# output_led.net
KiCad netlist of a schematic drawn in EAGLE
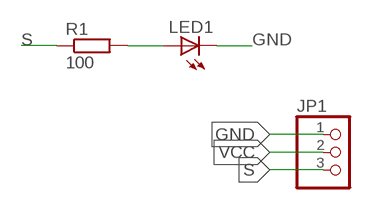
[diagram p0: schematic, sheet 1]

(export (version "E")
  (design (tool "Eeschema 10.0.6"))
  (components
    (comp (ref "JP1")
      (value "PINHD-1X3")
      (footprint "eagle-import:1X03")
      (libsource (lib "eagle-import") (part "PINHD-1X3"))
    )
    (comp (ref "LED1")
      (value "LED5MM")
      (footprint "eagle-import:LED5MM")
      (libsource (lib "eagle-import") (part "LED5MM"))
    )
    (comp (ref "R1")
      (value "100")
      (footprint "eagle-import:0204_7")
      (libsource (lib "eagle-import") (part "R-EU_0204/7"))
    )
  )
  (nets
    (net (code "1") (name "GND") (class "Default")
      (node (ref "JP1") (pin "1") (pinfunction "1_1") (pintype "passive"))
      (node (ref "LED1") (pin "K") (pinfunction "C_K") (pintype "passive"))
    )
    (net (code "2") (name "Net-(LED1-PadA)") (class "Default")
      (node (ref "LED1") (pin "A") (pinfunction "A_A") (pintype "passive"))
      (node (ref "R1") (pin "2") (pinfunction "2_2") (pintype "passive"))
    )
    (net (code "3") (name "S") (class "Default")
      (node (ref "JP1") (pin "3") (pinfunction "3_3") (pintype "passive"))
      (node (ref "R1") (pin "1") (pinfunction "1_1") (pintype "passive"))
    )
    (net (code "4") (name "VCC") (class "Default")
      (node (ref "JP1") (pin "2") (pinfunction "2_2") (pintype "passive"))
    )
  )
)
